# 8-Bit_Register.net
KiCad netlist of a schematic drawn in EAGLE
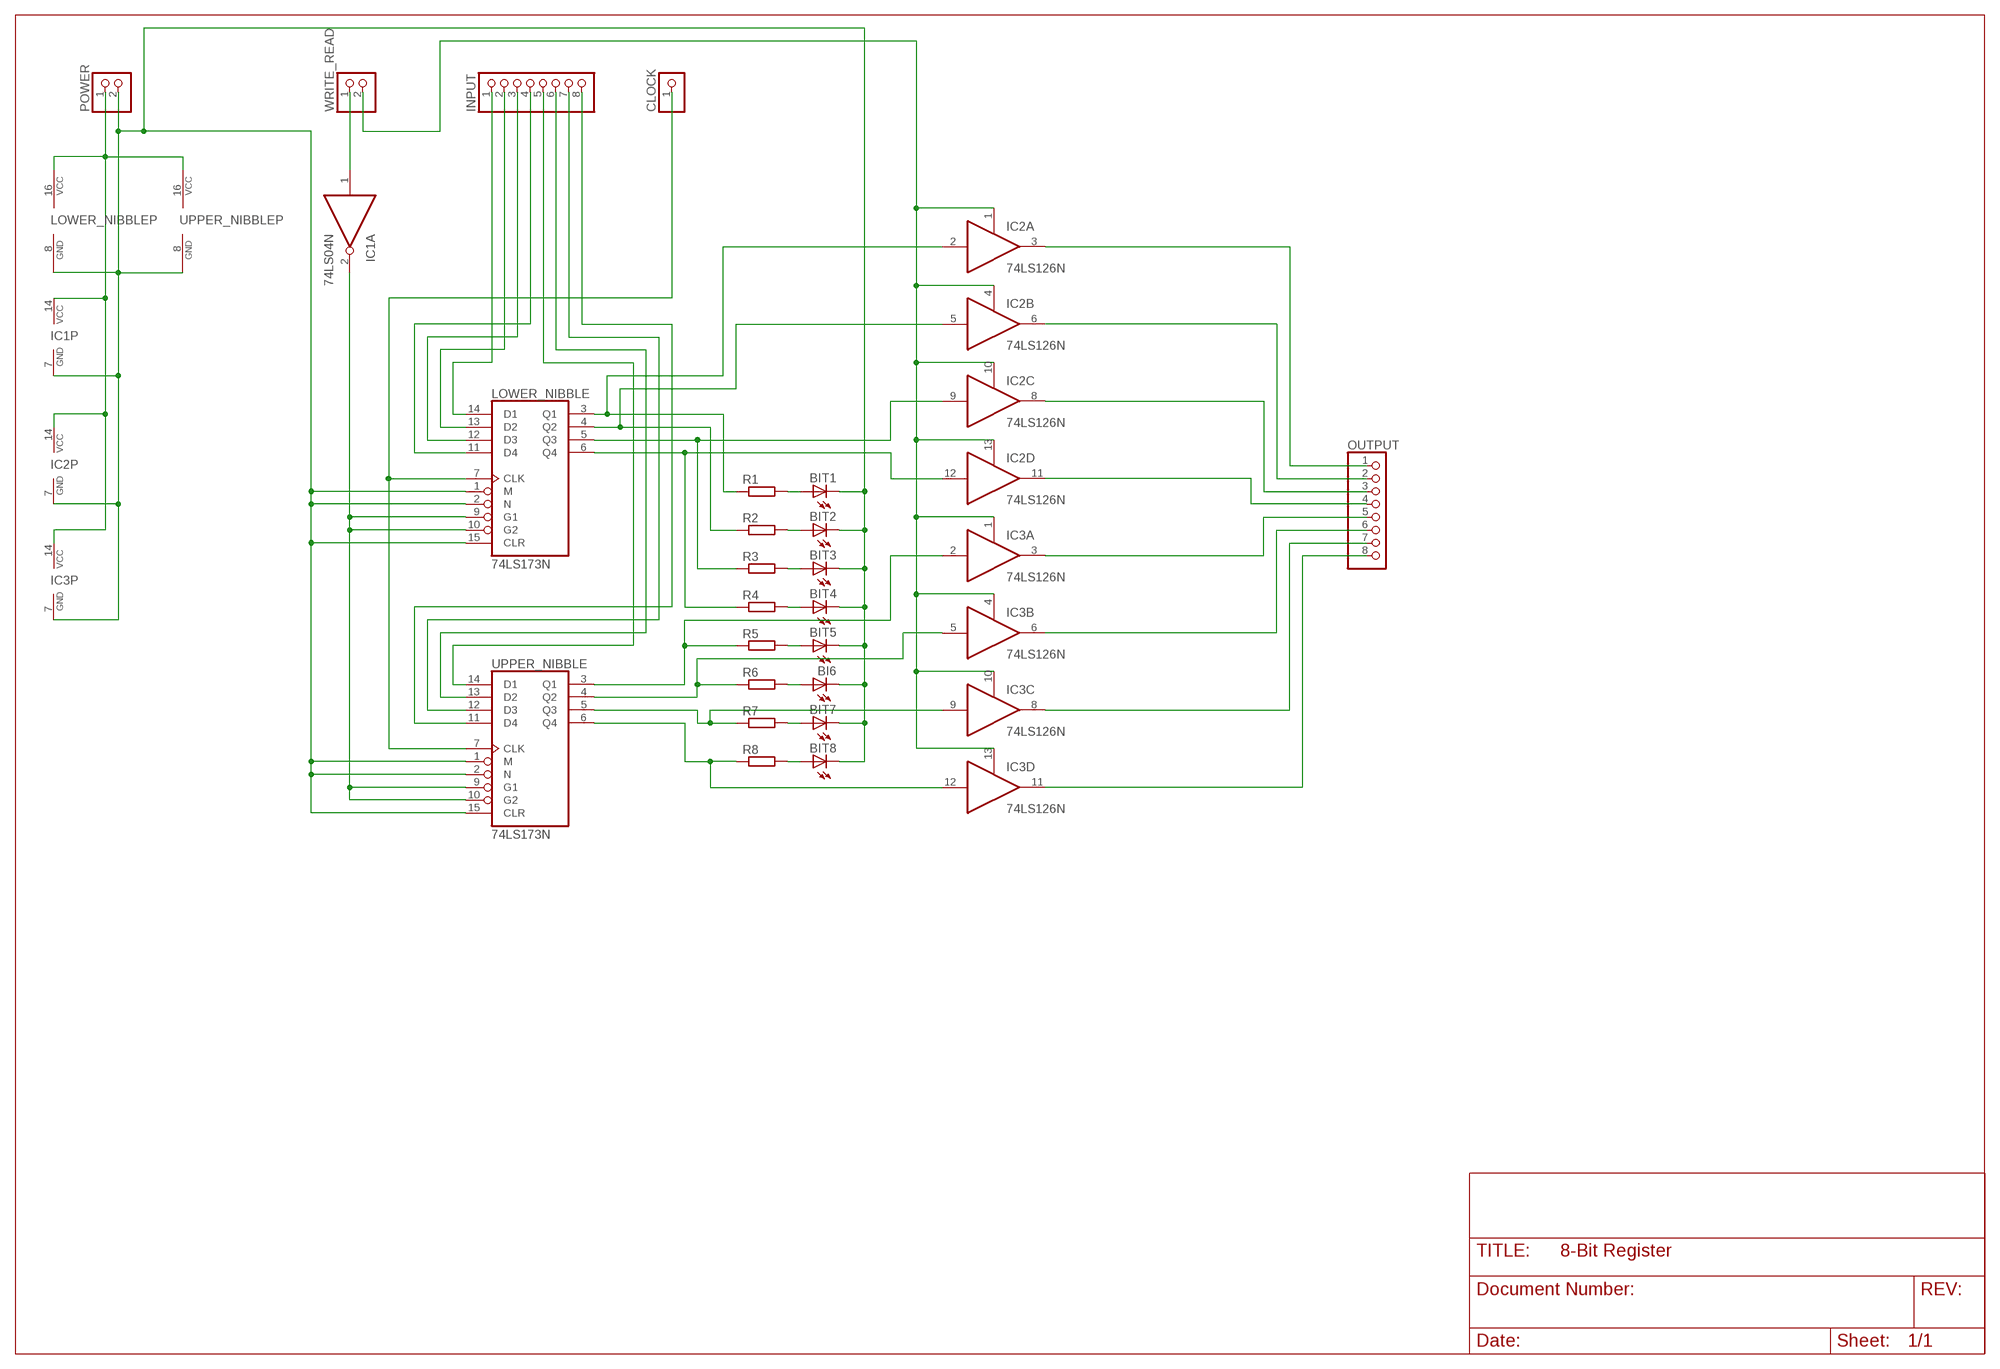
[diagram p0: schematic, sheet 1]

(export (version "E")
  (design (tool "Eeschema 10.0.6"))
  (components
    (comp (ref "BI6")
      (value "LED3MM")
      (footprint "eagle-import:LED3MM")
      (libsource (lib "eagle-import") (part "LED3MM"))
    )
    (comp (ref "BIT1")
      (value "LED3MM")
      (footprint "eagle-import:LED3MM")
      (libsource (lib "eagle-import") (part "LED3MM"))
    )
    (comp (ref "BIT2")
      (value "LED3MM")
      (footprint "eagle-import:LED3MM")
      (libsource (lib "eagle-import") (part "LED3MM"))
    )
    (comp (ref "BIT3")
      (value "LED3MM")
      (footprint "eagle-import:LED3MM")
      (libsource (lib "eagle-import") (part "LED3MM"))
    )
    (comp (ref "BIT4")
      (value "LED3MM")
      (footprint "eagle-import:LED3MM")
      (libsource (lib "eagle-import") (part "LED3MM"))
    )
    (comp (ref "BIT5")
      (value "LED3MM")
      (footprint "eagle-import:LED3MM")
      (libsource (lib "eagle-import") (part "LED3MM"))
    )
    (comp (ref "BIT7")
      (value "LED3MM")
      (footprint "eagle-import:LED3MM")
      (libsource (lib "eagle-import") (part "LED3MM"))
    )
    (comp (ref "BIT8")
      (value "LED3MM")
      (footprint "eagle-import:LED3MM")
      (libsource (lib "eagle-import") (part "LED3MM"))
    )
    (comp (ref "CLOCK")
      (value "PINHD-1X1")
      (footprint "eagle-import:1X01")
      (libsource (lib "eagle-import") (part "PINHD-1X1"))
    )
    (comp (ref "IC1")
      (value "74LS04N")
      (footprint "eagle-import:DIL14")
      (libsource (lib "eagle-import") (part "7404NLS"))
    )
    (comp (ref "IC2")
      (value "74LS126N")
      (footprint "eagle-import:DIL14")
      (libsource (lib "eagle-import") (part "74126NLS"))
    )
    (comp (ref "IC3")
      (value "74LS126N")
      (footprint "eagle-import:DIL14")
      (libsource (lib "eagle-import") (part "74126NLS"))
    )
    (comp (ref "INPUT")
      (value "PINHD-1X8")
      (footprint "eagle-import:1X08")
      (libsource (lib "eagle-import") (part "PINHD-1X8"))
    )
    (comp (ref "LOWER_NIBBLE")
      (value "74LS173N")
      (footprint "eagle-import:DIL16")
      (libsource (lib "eagle-import") (part "74173NLS"))
    )
    (comp (ref "OUTPUT")
      (value "PINHD-1X8")
      (footprint "eagle-import:1X08")
      (libsource (lib "eagle-import") (part "PINHD-1X8"))
    )
    (comp (ref "POWER")
      (value "PINHD-1X2")
      (footprint "eagle-import:1X02")
      (libsource (lib "eagle-import") (part "PINHD-1X2"))
    )
    (comp (ref "R1")
      (value "R-EU_0207/10")
      (footprint "eagle-import:0207_10")
      (libsource (lib "eagle-import") (part "R-EU_0207/10"))
    )
    (comp (ref "R2")
      (value "R-EU_0207/10")
      (footprint "eagle-import:0207_10")
      (libsource (lib "eagle-import") (part "R-EU_0207/10"))
    )
    (comp (ref "R3")
      (value "R-EU_0207/10")
      (footprint "eagle-import:0207_10")
      (libsource (lib "eagle-import") (part "R-EU_0207/10"))
    )
    (comp (ref "R4")
      (value "R-EU_0207/10")
      (footprint "eagle-import:0207_10")
      (libsource (lib "eagle-import") (part "R-EU_0207/10"))
    )
    (comp (ref "R5")
      (value "R-EU_0207/10")
      (footprint "eagle-import:0207_10")
      (libsource (lib "eagle-import") (part "R-EU_0207/10"))
    )
    (comp (ref "R6")
      (value "R-EU_0207/10")
      (footprint "eagle-import:0207_10")
      (libsource (lib "eagle-import") (part "R-EU_0207/10"))
    )
    (comp (ref "R7")
      (value "R-EU_0207/10")
      (footprint "eagle-import:0207_10")
      (libsource (lib "eagle-import") (part "R-EU_0207/10"))
    )
    (comp (ref "R8")
      (value "R-EU_0207/10")
      (footprint "eagle-import:0207_10")
      (libsource (lib "eagle-import") (part "R-EU_0207/10"))
    )
    (comp (ref "UPPER_NIBBLE")
      (value "74LS173N")
      (footprint "eagle-import:DIL16")
      (libsource (lib "eagle-import") (part "74173NLS"))
    )
    (comp (ref "WRITE_READ")
      (value "PINHD-1X2")
      (footprint "eagle-import:1X02")
      (libsource (lib "eagle-import") (part "PINHD-1X2"))
    )
  )
  (nets
    (net (code "1") (name "Net-(BI6-C)") (class "Default")
      (node (ref "BI6") (pin "K") (pinfunction "C_K") (pintype "passive"))
      (node (ref "BIT1") (pin "K") (pinfunction "C_K") (pintype "passive"))
      (node (ref "BIT2") (pin "K") (pinfunction "C_K") (pintype "passive"))
      (node (ref "BIT3") (pin "K") (pinfunction "C_K") (pintype "passive"))
      (node (ref "BIT4") (pin "K") (pinfunction "C_K") (pintype "passive"))
      (node (ref "BIT5") (pin "K") (pinfunction "C_K") (pintype "passive"))
      (node (ref "BIT7") (pin "K") (pinfunction "C_K") (pintype "passive"))
      (node (ref "BIT8") (pin "K") (pinfunction "C_K") (pintype "passive"))
      (node (ref "IC1") (pin "7") (pinfunction "GND_7") (pintype "power_in"))
      (node (ref "IC2") (pin "7") (pinfunction "GND_7") (pintype "power_in"))
      (node (ref "IC3") (pin "7") (pinfunction "GND_7") (pintype "power_in"))
      (node (ref "LOWER_NIBBLE") (pin "1") (pinfunction "M_1") (pintype "input"))
      (node (ref "LOWER_NIBBLE") (pin "15") (pinfunction "CLR_15") (pintype "input"))
      (node (ref "LOWER_NIBBLE") (pin "2") (pinfunction "N_2") (pintype "input"))
      (node (ref "LOWER_NIBBLE") (pin "8") (pinfunction "GND_8") (pintype "power_in"))
      (node (ref "POWER") (pin "2") (pinfunction "2_2") (pintype "passive"))
      (node (ref "UPPER_NIBBLE") (pin "1") (pinfunction "M_1") (pintype "input"))
      (node (ref "UPPER_NIBBLE") (pin "15") (pinfunction "CLR_15") (pintype "input"))
      (node (ref "UPPER_NIBBLE") (pin "2") (pinfunction "N_2") (pintype "input"))
      (node (ref "UPPER_NIBBLE") (pin "8") (pinfunction "GND_8") (pintype "power_in"))
    )
    (net (code "2") (name "Net-(BI6-PadA)") (class "Default")
      (node (ref "BI6") (pin "A") (pinfunction "A_A") (pintype "passive"))
      (node (ref "R6") (pin "2") (pinfunction "2_2") (pintype "passive"))
    )
    (net (code "3") (name "Net-(BIT1-PadA)") (class "Default")
      (node (ref "BIT1") (pin "A") (pinfunction "A_A") (pintype "passive"))
      (node (ref "R1") (pin "2") (pinfunction "2_2") (pintype "passive"))
    )
    (net (code "4") (name "Net-(BIT2-PadA)") (class "Default")
      (node (ref "BIT2") (pin "A") (pinfunction "A_A") (pintype "passive"))
      (node (ref "R2") (pin "2") (pinfunction "2_2") (pintype "passive"))
    )
    (net (code "5") (name "Net-(BIT3-PadA)") (class "Default")
      (node (ref "BIT3") (pin "A") (pinfunction "A_A") (pintype "passive"))
      (node (ref "R3") (pin "2") (pinfunction "2_2") (pintype "passive"))
    )
    (net (code "6") (name "Net-(BIT4-PadA)") (class "Default")
      (node (ref "BIT4") (pin "A") (pinfunction "A_A") (pintype "passive"))
      (node (ref "R4") (pin "2") (pinfunction "2_2") (pintype "passive"))
    )
    (net (code "7") (name "Net-(BIT5-PadA)") (class "Default")
      (node (ref "BIT5") (pin "A") (pinfunction "A_A") (pintype "passive"))
      (node (ref "R5") (pin "2") (pinfunction "2_2") (pintype "passive"))
    )
    (net (code "8") (name "Net-(BIT7-PadA)") (class "Default")
      (node (ref "BIT7") (pin "A") (pinfunction "A_A") (pintype "passive"))
      (node (ref "R7") (pin "2") (pinfunction "2_2") (pintype "passive"))
    )
    (net (code "9") (name "Net-(BIT8-PadA)") (class "Default")
      (node (ref "BIT8") (pin "A") (pinfunction "A_A") (pintype "passive"))
      (node (ref "R8") (pin "2") (pinfunction "2_2") (pintype "passive"))
    )
    (net (code "10") (name "Net-(IC1A-I)") (class "Default")
      (node (ref "IC1") (pin "1") (pinfunction "I_1") (pintype "input"))
      (node (ref "WRITE_READ") (pin "1") (pinfunction "1_1") (pintype "passive"))
    )
    (net (code "11") (name "Net-(IC1A-O)") (class "Default")
      (node (ref "IC1") (pin "2") (pinfunction "O_2") (pintype "output"))
      (node (ref "LOWER_NIBBLE") (pin "10") (pinfunction "G2_10") (pintype "input"))
      (node (ref "LOWER_NIBBLE") (pin "9") (pinfunction "G1_9") (pintype "input"))
      (node (ref "UPPER_NIBBLE") (pin "10") (pinfunction "G2_10") (pintype "input"))
      (node (ref "UPPER_NIBBLE") (pin "9") (pinfunction "G1_9") (pintype "input"))
    )
    (net (code "12") (name "Net-(IC1G-VCC)") (class "Default")
      (node (ref "IC1") (pin "14") (pinfunction "VCC_14") (pintype "power_in"))
      (node (ref "IC2") (pin "14") (pinfunction "VCC_14") (pintype "power_in"))
      (node (ref "IC3") (pin "14") (pinfunction "VCC_14") (pintype "power_in"))
      (node (ref "LOWER_NIBBLE") (pin "16") (pinfunction "VCC_16") (pintype "power_in"))
      (node (ref "POWER") (pin "1") (pinfunction "1_1") (pintype "passive"))
      (node (ref "UPPER_NIBBLE") (pin "16") (pinfunction "VCC_16") (pintype "power_in"))
    )
    (net (code "13") (name "Net-(IC2A-I)") (class "Default")
      (node (ref "IC2") (pin "2") (pinfunction "I_2") (pintype "input"))
      (node (ref "LOWER_NIBBLE") (pin "3") (pinfunction "Q1_3") (pintype "tri_state"))
      (node (ref "R1") (pin "1") (pinfunction "1_1") (pintype "passive"))
    )
    (net (code "14") (name "Net-(IC2A-O)") (class "Default")
      (node (ref "IC2") (pin "3") (pinfunction "O_3") (pintype "output"))
      (node (ref "OUTPUT") (pin "1") (pinfunction "1_1") (pintype "passive"))
    )
    (net (code "15") (name "Net-(IC2A-OE)") (class "Default")
      (node (ref "IC2") (pin "1") (pinfunction "OE_1") (pintype "input"))
      (node (ref "IC2") (pin "10") (pinfunction "OE_10") (pintype "input"))
      (node (ref "IC2") (pin "13") (pinfunction "OE_13") (pintype "input"))
      (node (ref "IC2") (pin "4") (pinfunction "OE_4") (pintype "input"))
      (node (ref "IC3") (pin "1") (pinfunction "OE_1") (pintype "input"))
      (node (ref "IC3") (pin "10") (pinfunction "OE_10") (pintype "input"))
      (node (ref "IC3") (pin "13") (pinfunction "OE_13") (pintype "input"))
      (node (ref "IC3") (pin "4") (pinfunction "OE_4") (pintype "input"))
      (node (ref "WRITE_READ") (pin "2") (pinfunction "2_2") (pintype "passive"))
    )
    (net (code "16") (name "Net-(IC2B-I)") (class "Default")
      (node (ref "IC2") (pin "5") (pinfunction "I_5") (pintype "input"))
      (node (ref "LOWER_NIBBLE") (pin "4") (pinfunction "Q2_4") (pintype "tri_state"))
      (node (ref "R2") (pin "1") (pinfunction "1_1") (pintype "passive"))
    )
    (net (code "17") (name "Net-(IC2B-O)") (class "Default")
      (node (ref "IC2") (pin "6") (pinfunction "O_6") (pintype "output"))
      (node (ref "OUTPUT") (pin "2") (pinfunction "2_2") (pintype "passive"))
    )
    (net (code "18") (name "Net-(IC2C-I)") (class "Default")
      (node (ref "IC2") (pin "9") (pinfunction "I_9") (pintype "input"))
      (node (ref "LOWER_NIBBLE") (pin "5") (pinfunction "Q3_5") (pintype "tri_state"))
      (node (ref "R3") (pin "1") (pinfunction "1_1") (pintype "passive"))
    )
    (net (code "19") (name "Net-(IC2C-O)") (class "Default")
      (node (ref "IC2") (pin "8") (pinfunction "O_8") (pintype "output"))
      (node (ref "OUTPUT") (pin "3") (pinfunction "3_3") (pintype "passive"))
    )
    (net (code "20") (name "Net-(IC2D-I)") (class "Default")
      (node (ref "IC2") (pin "12") (pinfunction "I_12") (pintype "input"))
      (node (ref "LOWER_NIBBLE") (pin "6") (pinfunction "Q4_6") (pintype "tri_state"))
      (node (ref "R4") (pin "1") (pinfunction "1_1") (pintype "passive"))
    )
    (net (code "21") (name "Net-(IC2D-O)") (class "Default")
      (node (ref "IC2") (pin "11") (pinfunction "O_11") (pintype "output"))
      (node (ref "OUTPUT") (pin "4") (pinfunction "4_4") (pintype "passive"))
    )
    (net (code "22") (name "Net-(IC3A-I)") (class "Default")
      (node (ref "IC3") (pin "2") (pinfunction "I_2") (pintype "input"))
      (node (ref "R5") (pin "1") (pinfunction "1_1") (pintype "passive"))
      (node (ref "UPPER_NIBBLE") (pin "3") (pinfunction "Q1_3") (pintype "tri_state"))
    )
    (net (code "23") (name "Net-(IC3A-O)") (class "Default")
      (node (ref "IC3") (pin "3") (pinfunction "O_3") (pintype "output"))
      (node (ref "OUTPUT") (pin "5") (pinfunction "5_5") (pintype "passive"))
    )
    (net (code "24") (name "Net-(IC3B-I)") (class "Default")
      (node (ref "IC3") (pin "5") (pinfunction "I_5") (pintype "input"))
      (node (ref "R6") (pin "1") (pinfunction "1_1") (pintype "passive"))
      (node (ref "UPPER_NIBBLE") (pin "4") (pinfunction "Q2_4") (pintype "tri_state"))
    )
    (net (code "25") (name "Net-(IC3B-O)") (class "Default")
      (node (ref "IC3") (pin "6") (pinfunction "O_6") (pintype "output"))
      (node (ref "OUTPUT") (pin "6") (pinfunction "6_6") (pintype "passive"))
    )
    (net (code "26") (name "Net-(IC3C-I)") (class "Default")
      (node (ref "IC3") (pin "9") (pinfunction "I_9") (pintype "input"))
      (node (ref "R7") (pin "1") (pinfunction "1_1") (pintype "passive"))
      (node (ref "UPPER_NIBBLE") (pin "5") (pinfunction "Q3_5") (pintype "tri_state"))
    )
    (net (code "27") (name "Net-(IC3C-O)") (class "Default")
      (node (ref "IC3") (pin "8") (pinfunction "O_8") (pintype "output"))
      (node (ref "OUTPUT") (pin "7") (pinfunction "7_7") (pintype "passive"))
    )
    (net (code "28") (name "Net-(IC3D-I)") (class "Default")
      (node (ref "IC3") (pin "12") (pinfunction "I_12") (pintype "input"))
      (node (ref "R8") (pin "1") (pinfunction "1_1") (pintype "passive"))
      (node (ref "UPPER_NIBBLE") (pin "6") (pinfunction "Q4_6") (pintype "tri_state"))
    )
    (net (code "29") (name "Net-(IC3D-O)") (class "Default")
      (node (ref "IC3") (pin "11") (pinfunction "O_11") (pintype "output"))
      (node (ref "OUTPUT") (pin "8") (pinfunction "8_8") (pintype "passive"))
    )
    (net (code "30") (name "Net-(LOWER_NIBBLEA-CLK)") (class "Default")
      (node (ref "CLOCK") (pin "1") (pinfunction "1_1") (pintype "passive"))
      (node (ref "LOWER_NIBBLE") (pin "7") (pinfunction "CLK_7") (pintype "input"))
      (node (ref "UPPER_NIBBLE") (pin "7") (pinfunction "CLK_7") (pintype "input"))
    )
    (net (code "31") (name "Net-(LOWER_NIBBLEA-D1)") (class "Default")
      (node (ref "INPUT") (pin "1") (pinfunction "1_1") (pintype "passive"))
      (node (ref "LOWER_NIBBLE") (pin "14") (pinfunction "D1_14") (pintype "input"))
    )
    (net (code "32") (name "Net-(LOWER_NIBBLEA-D2)") (class "Default")
      (node (ref "INPUT") (pin "2") (pinfunction "2_2") (pintype "passive"))
      (node (ref "LOWER_NIBBLE") (pin "13") (pinfunction "D2_13") (pintype "input"))
    )
    (net (code "33") (name "Net-(LOWER_NIBBLEA-D3)") (class "Default")
      (node (ref "INPUT") (pin "3") (pinfunction "3_3") (pintype "passive"))
      (node (ref "LOWER_NIBBLE") (pin "12") (pinfunction "D3_12") (pintype "input"))
    )
    (net (code "34") (name "Net-(LOWER_NIBBLEA-D4)") (class "Default")
      (node (ref "INPUT") (pin "4") (pinfunction "4_4") (pintype "passive"))
      (node (ref "LOWER_NIBBLE") (pin "11") (pinfunction "D4_11") (pintype "input"))
    )
    (net (code "35") (name "Net-(UPPER_NIBBLEA-D1)") (class "Default")
      (node (ref "INPUT") (pin "5") (pinfunction "5_5") (pintype "passive"))
      (node (ref "UPPER_NIBBLE") (pin "14") (pinfunction "D1_14") (pintype "input"))
    )
    (net (code "36") (name "Net-(UPPER_NIBBLEA-D2)") (class "Default")
      (node (ref "INPUT") (pin "6") (pinfunction "6_6") (pintype "passive"))
      (node (ref "UPPER_NIBBLE") (pin "13") (pinfunction "D2_13") (pintype "input"))
    )
    (net (code "37") (name "Net-(UPPER_NIBBLEA-D3)") (class "Default")
      (node (ref "INPUT") (pin "7") (pinfunction "7_7") (pintype "passive"))
      (node (ref "UPPER_NIBBLE") (pin "12") (pinfunction "D3_12") (pintype "input"))
    )
    (net (code "38") (name "Net-(UPPER_NIBBLEA-D4)") (class "Default")
      (node (ref "INPUT") (pin "8") (pinfunction "8_8") (pintype "passive"))
      (node (ref "UPPER_NIBBLE") (pin "11") (pinfunction "D4_11") (pintype "input"))
    )
  )
)
